# espDownloadBoard.net
KiCad netlist of a schematic drawn in Altium Designer
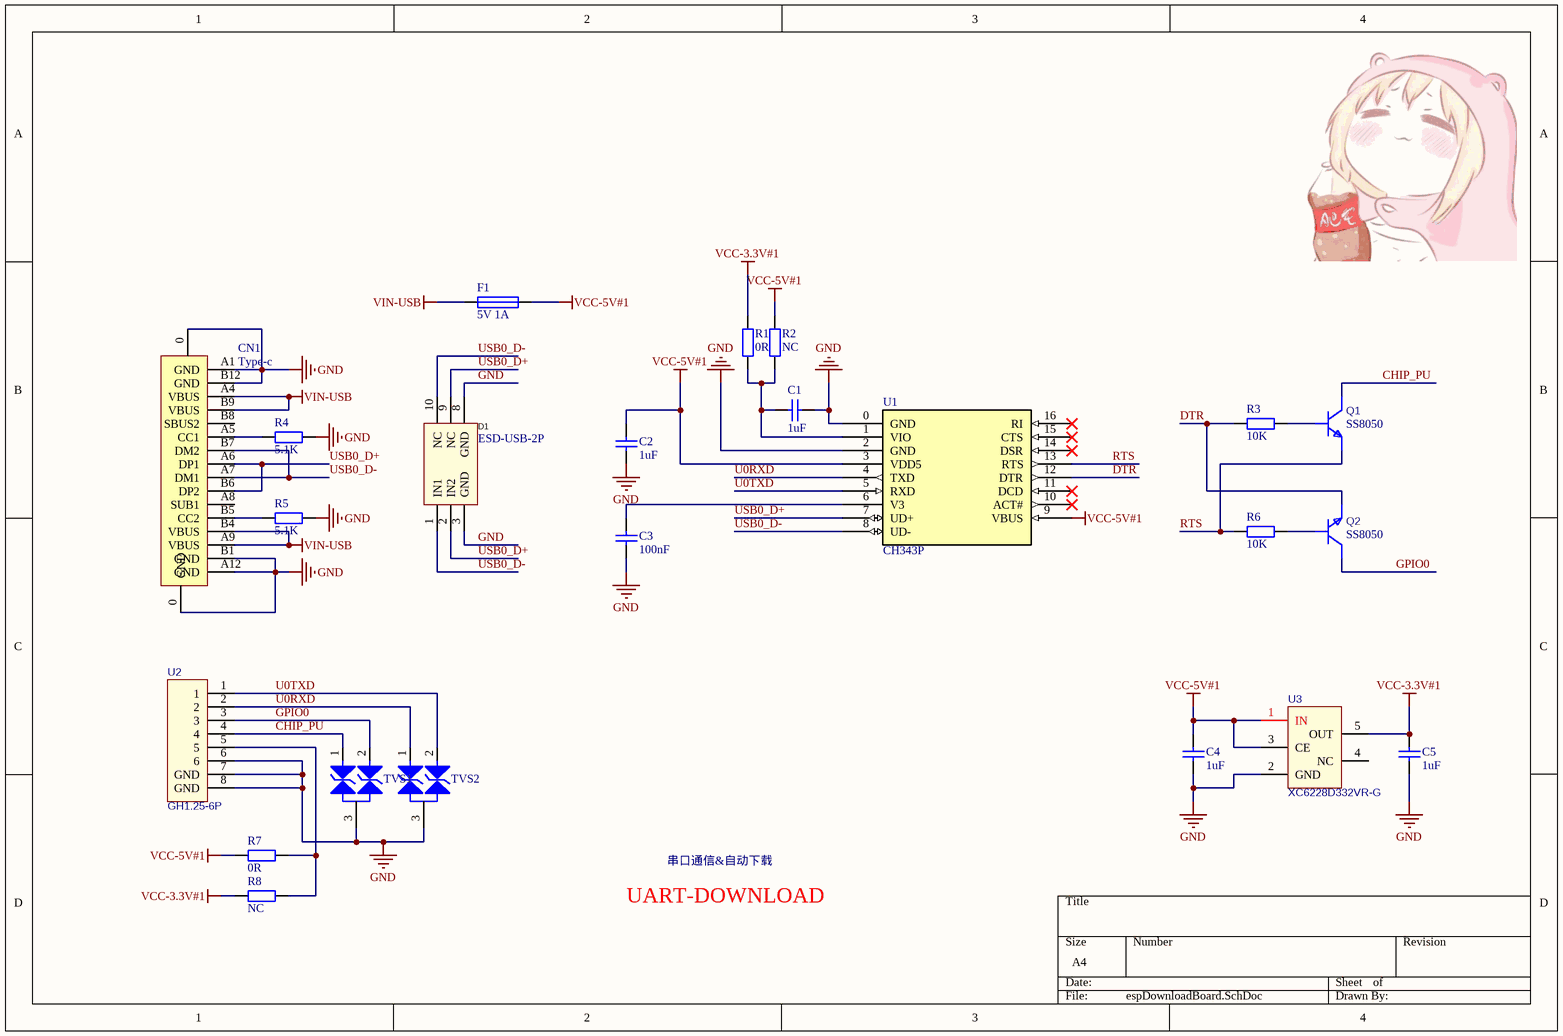
[diagram p0: espDownloadBoard.SchDoc]

(export (version "E")
  (design (tool "Eeschema 10.0.6"))
  (components
    (comp (ref "C1")
      (value "1uF")
      (footprint "0603-C")
      (description "贴片电容")
      (libsource (lib "封装库") (part "C"))
    )
    (comp (ref "C2")
      (value "1uF")
      (footprint "0603-C")
      (description "贴片电容")
      (libsource (lib "封装库") (part "C"))
    )
    (comp (ref "C3")
      (value "100nF")
      (footprint "0603-C")
      (description "贴片电容")
      (libsource (lib "封装库") (part "C"))
    )
    (comp (ref "C4")
      (value "1uF")
      (footprint "0603-C")
      (description "贴片电容")
      (libsource (lib "封装库") (part "C"))
    )
    (comp (ref "C5")
      (value "1uF")
      (footprint "0603-C")
      (description "贴片电容")
      (libsource (lib "封装库") (part "C"))
    )
    (comp (ref "CN1")
      (value "Type-c")
      (footprint "Type-c 16pin")
      (description "U262-161N-4BVC11")
      (libsource (lib "封装") (part "Type-c"))
    )
    (comp (ref "D1")
      (value "ESD-USB-2P")
      (footprint "SLP2510P8-2P")
      (description "RClamp0522PATCT")
      (fields (field (name "MANUFACTURER") "SEMTECH") (field (name "MANUFACTURER PART") "RClamp0524PATCT"))
      (libsource (lib "封装库") (part "ESD-USB-2P"))
    )
    (comp (ref "F1")
      (value "5V 1A")
      (footprint "0805-R")
      (description "自恢复保险丝")
      (libsource (lib "封装库") (part "FUSE"))
    )
    (comp (ref "Q1") (value "SS8050") (footprint "SOT23-3M") (libsource (lib "封装库") (part "SS8050")))
    (comp (ref "Q2") (value "SS8050") (footprint "SOT23-3M") (libsource (lib "封装库") (part "SS8050")))
    (comp (ref "R1")
      (value "0R")
      (footprint "0603-R")
      (description "贴片电阻")
      (libsource (lib "封装库") (part "R"))
    )
    (comp (ref "R2")
      (value "NC")
      (footprint "0603-R")
      (description "贴片电阻")
      (libsource (lib "封装库") (part "R"))
    )
    (comp (ref "R3")
      (value "10K")
      (footprint "0603-R")
      (description "贴片电阻")
      (libsource (lib "封装库") (part "R"))
    )
    (comp (ref "R4")
      (value "5.1K")
      (footprint "0603-R")
      (description "贴片电阻")
      (libsource (lib "封装库") (part "R"))
    )
    (comp (ref "R5")
      (value "5.1K")
      (footprint "0603-R")
      (description "贴片电阻")
      (libsource (lib "封装库") (part "R"))
    )
    (comp (ref "R6")
      (value "10K")
      (footprint "0603-R")
      (description "贴片电阻")
      (libsource (lib "封装库") (part "R"))
    )
    (comp (ref "R7")
      (value "0R")
      (footprint "0603-R")
      (description "贴片电阻")
      (libsource (lib "封装库") (part "R"))
    )
    (comp (ref "R8")
      (value "NC")
      (footprint "0603-R")
      (description "贴片电阻")
      (libsource (lib "封装库") (part "R"))
    )
    (comp (ref "TVS1") (value "ESDA5V3L") (footprint "ESDA5V3L") (libsource (lib "封装库") (part "ESDA5V3L")))
    (comp (ref "TVS2") (value "ESDA5V3L") (footprint "ESDA5V3L") (libsource (lib "封装库") (part "ESDA5V3L")))
    (comp (ref "U1")
      (value "CH343P")
      (footprint "QFN16_3X3")
      (description "USB to high speed enhanced TTL Serial / UART")
      (libsource (lib "封装库") (part "CH343P"))
    )
    (comp (ref "U2")
      (value "GH1.25-6P")
      (footprint "CONN-SMD_A1257WR-S-6P")
      (description "GH1.25-4PWBPZ")
      (fields (field (name "BOM_SUPPLIER PART") "C2829253") (field (name "CONTRIBUTOR") "LCSC"))
      (libsource (lib "封装库") (part "GH1.25-6P"))
    )
    (comp (ref "U3")
      (value "XC6228D332VR-G")
      (footprint "XC6228D332VR-G")
      (fields (field (name "BOM_SUPPLIER PART") "C69841"))
      (libsource (lib "封装库") (part "XC6228D332VR-G"))
    )
  )
  (nets
    (net (code "1") (name "/CHIP_PU") (class "Default")
      (node (ref "Q1") (pin "3") (pinfunction "C_3") (pintype "passive"))
      (node (ref "TVS1") (pin "1") (pinfunction "K_1") (pintype "passive"))
      (node (ref "U2") (pin "4") (pinfunction "4_4") (pintype "passive"))
    )
    (net (code "2") (name "/DTR") (class "Default")
      (node (ref "Q2") (pin "2") (pinfunction "E_2") (pintype "passive"))
      (node (ref "R3") (pin "1") (pinfunction "1_1") (pintype "passive"))
      (node (ref "U1") (pin "12") (pinfunction "DTR_12") (pintype "output"))
    )
    (net (code "3") (name "/GPIO0") (class "Default")
      (node (ref "Q2") (pin "3") (pinfunction "C_3") (pintype "passive"))
      (node (ref "TVS1") (pin "2") (pinfunction "A_2") (pintype "passive"))
      (node (ref "U2") (pin "3") (pinfunction "3_3") (pintype "passive"))
    )
    (net (code "4") (name "/RTS") (class "Default")
      (node (ref "Q1") (pin "2") (pinfunction "E_2") (pintype "passive"))
      (node (ref "R6") (pin "1") (pinfunction "1_1") (pintype "passive"))
      (node (ref "U1") (pin "13") (pinfunction "RTS_13") (pintype "output"))
    )
    (net (code "5") (name "/U0RXD") (class "Default")
      (node (ref "TVS2") (pin "1") (pinfunction "K_1") (pintype "passive"))
      (node (ref "U1") (pin "4") (pinfunction "TXD_4") (pintype "output"))
      (node (ref "U2") (pin "2") (pinfunction "2_2") (pintype "passive"))
    )
    (net (code "6") (name "/U0TXD") (class "Default")
      (node (ref "TVS2") (pin "2") (pinfunction "A_2") (pintype "passive"))
      (node (ref "U1") (pin "5") (pinfunction "RXD_5") (pintype "input"))
      (node (ref "U2") (pin "1") (pinfunction "1_1") (pintype "passive"))
    )
    (net (code "7") (name "/USB0_D+") (class "Default")
      (node (ref "CN1") (pin "A6") (pinfunction "DP1_A6") (pintype "passive"))
      (node (ref "CN1") (pin "B6") (pinfunction "DP2_B6") (pintype "passive"))
      (node (ref "D1") (pin "2") (pinfunction "IN2_2") (pintype "passive"))
      (node (ref "D1") (pin "9") (pinfunction "NC_9") (pintype "passive"))
      (node (ref "U1") (pin "7") (pinfunction "UD+_7") (pintype "bidirectional"))
    )
    (net (code "8") (name "/USB0_D-") (class "Default")
      (node (ref "CN1") (pin "A7") (pinfunction "DM1_A7") (pintype "passive"))
      (node (ref "CN1") (pin "B7") (pinfunction "DM2_B7") (pintype "passive"))
      (node (ref "D1") (pin "1") (pinfunction "IN1_1") (pintype "passive"))
      (node (ref "D1") (pin "10") (pinfunction "NC_10") (pintype "passive"))
      (node (ref "U1") (pin "8") (pinfunction "UD-_8") (pintype "bidirectional"))
    )
    (net (code "9") (name "GND") (class "Default")
      (node (ref "C1") (pin "2") (pinfunction "2_2") (pintype "passive"))
      (node (ref "C2") (pin "2") (pinfunction "2_2") (pintype "passive"))
      (node (ref "C3") (pin "2") (pinfunction "2_2") (pintype "passive"))
      (node (ref "C4") (pin "1") (pinfunction "1_1") (pintype "passive"))
      (node (ref "C5") (pin "1") (pinfunction "1_1") (pintype "passive"))
      (node (ref "CN1") (pin "0") (pinfunction "GND_0") (pintype "passive"))
      (node (ref "CN1") (pin "A1") (pinfunction "GND_A1") (pintype "passive"))
      (node (ref "CN1") (pin "A12") (pinfunction "GND_A12") (pintype "passive"))
      (node (ref "CN1") (pin "B1") (pinfunction "GND_B1") (pintype "passive"))
      (node (ref "CN1") (pin "B12") (pinfunction "GND_B12") (pintype "passive"))
      (node (ref "D1") (pin "3") (pinfunction "GND_3") (pintype "passive"))
      (node (ref "D1") (pin "8") (pinfunction "GND_8") (pintype "passive"))
      (node (ref "R4") (pin "2") (pinfunction "2_2") (pintype "passive"))
      (node (ref "R5") (pin "2") (pinfunction "2_2") (pintype "passive"))
      (node (ref "TVS1") (pin "3") (pinfunction "K_3") (pintype "passive"))
      (node (ref "TVS2") (pin "3") (pinfunction "K_3") (pintype "passive"))
      (node (ref "U1") (pin "0") (pinfunction "GND_0") (pintype "power_in"))
      (node (ref "U1") (pin "2") (pinfunction "GND_2") (pintype "power_in"))
      (node (ref "U2") (pin "6") (pinfunction "6_6") (pintype "passive"))
      (node (ref "U2") (pin "7") (pinfunction "GND_7") (pintype "passive"))
      (node (ref "U2") (pin "8") (pinfunction "GND_8") (pintype "passive"))
      (node (ref "U3") (pin "2") (pinfunction "GND_2") (pintype "passive"))
    )
    (net (code "10") (name "Net-(CN1-CC1)") (class "Default")
      (node (ref "CN1") (pin "A5") (pinfunction "CC1_A5") (pintype "passive"))
      (node (ref "R4") (pin "1") (pinfunction "1_1") (pintype "passive"))
    )
    (net (code "11") (name "Net-(CN1-CC2)") (class "Default")
      (node (ref "CN1") (pin "B5") (pinfunction "CC2_B5") (pintype "passive"))
      (node (ref "R5") (pin "1") (pinfunction "1_1") (pintype "passive"))
    )
    (net (code "12") (name "Net-(Q1-B)") (class "Default")
      (node (ref "Q1") (pin "1") (pinfunction "B_1") (pintype "passive"))
      (node (ref "R3") (pin "2") (pinfunction "2_2") (pintype "passive"))
    )
    (net (code "13") (name "Net-(Q2-B)") (class "Default")
      (node (ref "Q2") (pin "1") (pinfunction "B_1") (pintype "passive"))
      (node (ref "R6") (pin "2") (pinfunction "2_2") (pintype "passive"))
    )
    (net (code "14") (name "Net-(R7-Pad1)") (class "Default")
      (node (ref "R7") (pin "1") (pinfunction "1_1") (pintype "passive"))
      (node (ref "R8") (pin "1") (pinfunction "1_1") (pintype "passive"))
      (node (ref "U2") (pin "5") (pinfunction "5_5") (pintype "passive"))
    )
    (net (code "15") (name "Net-(U1-V3)") (class "Default")
      (node (ref "C3") (pin "1") (pinfunction "1_1") (pintype "passive"))
      (node (ref "U1") (pin "6") (pinfunction "V3_6") (pintype "power_in"))
    )
    (net (code "16") (name "Net-(U1-VIO)") (class "Default")
      (node (ref "C1") (pin "1") (pinfunction "1_1") (pintype "passive"))
      (node (ref "R1") (pin "1") (pinfunction "1_1") (pintype "passive"))
      (node (ref "R2") (pin "1") (pinfunction "1_1") (pintype "passive"))
      (node (ref "U1") (pin "1") (pinfunction "VIO_1") (pintype "power_in"))
    )
    (net (code "17") (name "VCC-3.3V#1") (class "Default")
      (node (ref "C5") (pin "2") (pinfunction "2_2") (pintype "passive"))
      (node (ref "R1") (pin "2") (pinfunction "2_2") (pintype "passive"))
      (node (ref "R8") (pin "2") (pinfunction "2_2") (pintype "passive"))
      (node (ref "U3") (pin "5") (pinfunction "OUT_5") (pintype "passive"))
    )
    (net (code "18") (name "VCC-5V#1") (class "Default")
      (node (ref "C2") (pin "1") (pinfunction "1_1") (pintype "passive"))
      (node (ref "C4") (pin "2") (pinfunction "2_2") (pintype "passive"))
      (node (ref "F1") (pin "1") (pinfunction "1_1") (pintype "passive"))
      (node (ref "R2") (pin "2") (pinfunction "2_2") (pintype "passive"))
      (node (ref "R7") (pin "2") (pinfunction "2_2") (pintype "passive"))
      (node (ref "U1") (pin "3") (pinfunction "VDD5_3") (pintype "power_in"))
      (node (ref "U1") (pin "9") (pinfunction "VBUS_9") (pintype "input"))
      (node (ref "U3") (pin "1") (pinfunction "IN_1") (pintype "passive"))
      (node (ref "U3") (pin "3") (pinfunction "CE_3") (pintype "passive"))
    )
    (net (code "19") (name "VIN-USB") (class "Default")
      (node (ref "CN1") (pin "A4") (pinfunction "VBUS_A4") (pintype "passive"))
      (node (ref "CN1") (pin "A9") (pinfunction "VBUS_A9") (pintype "passive"))
      (node (ref "CN1") (pin "B4") (pinfunction "VBUS_B4") (pintype "passive"))
      (node (ref "CN1") (pin "B9") (pinfunction "VBUS_B9") (pintype "passive"))
      (node (ref "F1") (pin "2") (pinfunction "2_2") (pintype "passive"))
    )
    (net (code "20") (name "unconnected-(CN1-SBUS2-PadB8)") (class "Default")
      (node (ref "CN1") (pin "B8") (pinfunction "SBUS2_B8") (pintype "passive"))
    )
    (net (code "21") (name "unconnected-(CN1-SUB1-PadA8)") (class "Default")
      (node (ref "CN1") (pin "A8") (pinfunction "SUB1_A8") (pintype "passive"))
    )
    (net (code "22") (name "unconnected-(U1-ACT#-Pad10)") (class "Default")
      (node (ref "U1") (pin "10") (pinfunction "ACT#_10") (pintype "output+no_connect"))
    )
    (net (code "23") (name "unconnected-(U1-CTS-Pad15)") (class "Default")
      (node (ref "U1") (pin "15") (pinfunction "CTS_15") (pintype "input+no_connect"))
    )
    (net (code "24") (name "unconnected-(U1-DCD-Pad11)") (class "Default")
      (node (ref "U1") (pin "11") (pinfunction "DCD_11") (pintype "input+no_connect"))
    )
    (net (code "25") (name "unconnected-(U1-DSR-Pad14)") (class "Default")
      (node (ref "U1") (pin "14") (pinfunction "DSR_14") (pintype "input+no_connect"))
    )
    (net (code "26") (name "unconnected-(U1-RI-Pad16)") (class "Default")
      (node (ref "U1") (pin "16") (pinfunction "RI_16") (pintype "input+no_connect"))
    )
    (net (code "27") (name "unconnected-(U3-NC-Pad4)") (class "Default")
      (node (ref "U3") (pin "4") (pinfunction "NC_4") (pintype "passive"))
    )
  )
)
